# 4_serial_LSA.net
KiCad netlist of a schematic drawn in EAGLE
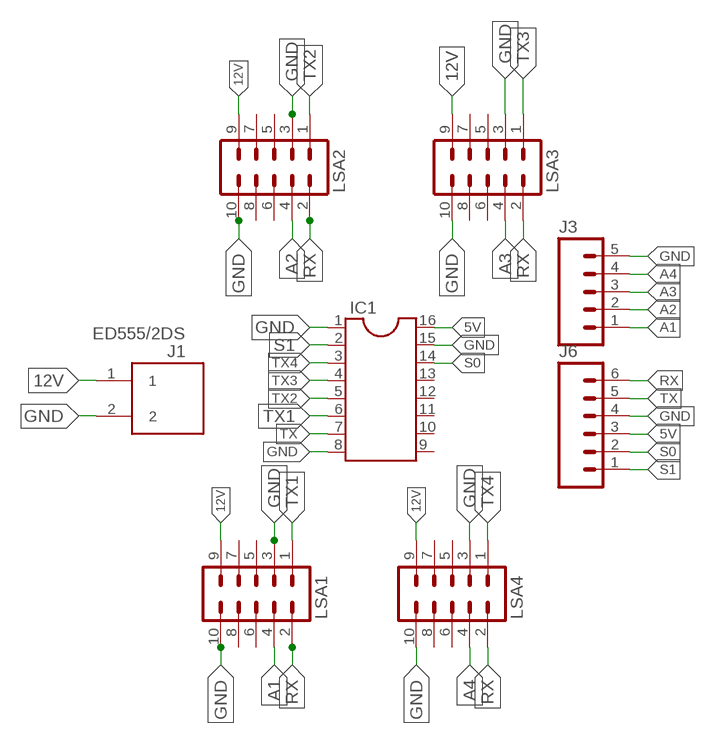
[diagram p0: schematic, sheet 1]

(export (version "E")
  (design (tool "Eeschema 10.0.6"))
  (components
    (comp (ref "IC1")
      (value "DIL16S")
      (footprint "eagle-import:SOCKET-16")
      (libsource (lib "eagle-import") (part "DIL16S"))
    )
    (comp (ref "J1")
      (value "ED555/2DS")
      (footprint "eagle-import:ED555_2DS")
      (libsource (lib "eagle-import") (part "ED555/2DS"))
    )
    (comp (ref "J3")
      (value "M05PTH")
      (footprint "eagle-import:1X05")
      (fields (field (name "SPICEPREFIX") "X"))
      (libsource (lib "eagle-import") (part "M05PTH"))
    )
    (comp (ref "J6")
      (value "M06SILK_FEMALE_PTH")
      (footprint "eagle-import:1X06")
      (libsource (lib "eagle-import") (part "M06SILK_FEMALE_PTH"))
    )
    (comp (ref "LSA1")
      (value "M05X2SHD_LOCK")
      (footprint "eagle-import:2X5-SHROUDED_LOCK")
      (libsource (lib "eagle-import") (part "M05X2SHD_LOCK"))
    )
    (comp (ref "LSA2")
      (value "M05X2SHD_LOCK")
      (footprint "eagle-import:2X5-SHROUDED_LOCK")
      (libsource (lib "eagle-import") (part "M05X2SHD_LOCK"))
    )
    (comp (ref "LSA3")
      (value "M05X2SHD_LOCK")
      (footprint "eagle-import:2X5-SHROUDED_LOCK")
      (libsource (lib "eagle-import") (part "M05X2SHD_LOCK"))
    )
    (comp (ref "LSA4")
      (value "M05X2SHD_LOCK")
      (footprint "eagle-import:2X5-SHROUDED_LOCK")
      (libsource (lib "eagle-import") (part "M05X2SHD_LOCK"))
    )
  )
  (nets
    (net (code "1") (name "5V") (class "Default")
      (node (ref "IC1") (pin "16") (pinfunction "16_16") (pintype "passive"))
      (node (ref "J6") (pin "3") (pinfunction "3_3") (pintype "passive"))
    )
    (net (code "2") (name "12V") (class "Default")
      (node (ref "J1") (pin "1") (pinfunction "1_1") (pintype "bidirectional"))
      (node (ref "LSA1") (pin "9") (pinfunction "9_9") (pintype "passive"))
      (node (ref "LSA2") (pin "9") (pinfunction "9_9") (pintype "passive"))
      (node (ref "LSA3") (pin "9") (pinfunction "9_9") (pintype "passive"))
      (node (ref "LSA4") (pin "9") (pinfunction "9_9") (pintype "passive"))
    )
    (net (code "3") (name "A1") (class "Default")
      (node (ref "J3") (pin "1") (pinfunction "1_1") (pintype "passive"))
      (node (ref "LSA1") (pin "4") (pinfunction "4_4") (pintype "passive"))
    )
    (net (code "4") (name "A2") (class "Default")
      (node (ref "J3") (pin "2") (pinfunction "2_2") (pintype "passive"))
      (node (ref "LSA2") (pin "4") (pinfunction "4_4") (pintype "passive"))
    )
    (net (code "5") (name "A3") (class "Default")
      (node (ref "J3") (pin "3") (pinfunction "3_3") (pintype "passive"))
      (node (ref "LSA3") (pin "4") (pinfunction "4_4") (pintype "passive"))
    )
    (net (code "6") (name "A4") (class "Default")
      (node (ref "J3") (pin "4") (pinfunction "4_4") (pintype "passive"))
      (node (ref "LSA4") (pin "4") (pinfunction "4_4") (pintype "passive"))
    )
    (net (code "7") (name "GND") (class "Default")
      (node (ref "IC1") (pin "1") (pinfunction "1_1") (pintype "passive"))
      (node (ref "IC1") (pin "15") (pinfunction "15_15") (pintype "passive"))
      (node (ref "IC1") (pin "8") (pinfunction "8_8") (pintype "passive"))
      (node (ref "J1") (pin "2") (pinfunction "2_2") (pintype "bidirectional"))
      (node (ref "J3") (pin "5") (pinfunction "5_5") (pintype "passive"))
      (node (ref "J6") (pin "4") (pinfunction "4_4") (pintype "passive"))
      (node (ref "LSA1") (pin "10") (pinfunction "10_10") (pintype "passive"))
      (node (ref "LSA1") (pin "3") (pinfunction "3_3") (pintype "passive"))
      (node (ref "LSA2") (pin "10") (pinfunction "10_10") (pintype "passive"))
      (node (ref "LSA2") (pin "3") (pinfunction "3_3") (pintype "passive"))
      (node (ref "LSA3") (pin "10") (pinfunction "10_10") (pintype "passive"))
      (node (ref "LSA3") (pin "3") (pinfunction "3_3") (pintype "passive"))
      (node (ref "LSA4") (pin "10") (pinfunction "10_10") (pintype "passive"))
      (node (ref "LSA4") (pin "3") (pinfunction "3_3") (pintype "passive"))
    )
    (net (code "8") (name "RX") (class "Default")
      (node (ref "J6") (pin "6") (pinfunction "6_6") (pintype "passive"))
      (node (ref "LSA1") (pin "2") (pinfunction "2_2") (pintype "passive"))
      (node (ref "LSA2") (pin "2") (pinfunction "2_2") (pintype "passive"))
      (node (ref "LSA3") (pin "2") (pinfunction "2_2") (pintype "passive"))
      (node (ref "LSA4") (pin "2") (pinfunction "2_2") (pintype "passive"))
    )
    (net (code "9") (name "S0") (class "Default")
      (node (ref "IC1") (pin "14") (pinfunction "14_14") (pintype "passive"))
      (node (ref "J6") (pin "2") (pinfunction "2_2") (pintype "passive"))
    )
    (net (code "10") (name "S1") (class "Default")
      (node (ref "IC1") (pin "2") (pinfunction "2_2") (pintype "passive"))
      (node (ref "J6") (pin "1") (pinfunction "1_1") (pintype "passive"))
    )
    (net (code "11") (name "TX") (class "Default")
      (node (ref "IC1") (pin "7") (pinfunction "7_7") (pintype "passive"))
      (node (ref "J6") (pin "5") (pinfunction "5_5") (pintype "passive"))
    )
    (net (code "12") (name "TX1") (class "Default")
      (node (ref "IC1") (pin "6") (pinfunction "6_6") (pintype "passive"))
      (node (ref "LSA1") (pin "1") (pinfunction "1_1") (pintype "passive"))
    )
    (net (code "13") (name "TX2") (class "Default")
      (node (ref "IC1") (pin "5") (pinfunction "5_5") (pintype "passive"))
      (node (ref "LSA2") (pin "1") (pinfunction "1_1") (pintype "passive"))
    )
    (net (code "14") (name "TX3") (class "Default")
      (node (ref "IC1") (pin "4") (pinfunction "4_4") (pintype "passive"))
      (node (ref "LSA3") (pin "1") (pinfunction "1_1") (pintype "passive"))
    )
    (net (code "15") (name "TX4") (class "Default")
      (node (ref "IC1") (pin "3") (pinfunction "3_3") (pintype "passive"))
      (node (ref "LSA4") (pin "1") (pinfunction "1_1") (pintype "passive"))
    )
    (net (code "16") (name "unconnected-(IC1-Pad9)") (class "Default")
      (node (ref "IC1") (pin "9") (pinfunction "9_9") (pintype "passive"))
    )
    (net (code "17") (name "unconnected-(IC1-Pad10)") (class "Default")
      (node (ref "IC1") (pin "10") (pinfunction "10_10") (pintype "passive"))
    )
    (net (code "18") (name "unconnected-(IC1-Pad11)") (class "Default")
      (node (ref "IC1") (pin "11") (pinfunction "11_11") (pintype "passive"))
    )
    (net (code "19") (name "unconnected-(IC1-Pad12)") (class "Default")
      (node (ref "IC1") (pin "12") (pinfunction "12_12") (pintype "passive"))
    )
    (net (code "20") (name "unconnected-(IC1-Pad13)") (class "Default")
      (node (ref "IC1") (pin "13") (pinfunction "13_13") (pintype "passive"))
    )
    (net (code "21") (name "unconnected-(LSA1-Pad5)") (class "Default")
      (node (ref "LSA1") (pin "5") (pinfunction "5_5") (pintype "passive"))
    )
    (net (code "22") (name "unconnected-(LSA1-Pad6)") (class "Default")
      (node (ref "LSA1") (pin "6") (pinfunction "6_6") (pintype "passive"))
    )
    (net (code "23") (name "unconnected-(LSA1-Pad7)") (class "Default")
      (node (ref "LSA1") (pin "7") (pinfunction "7_7") (pintype "passive"))
    )
    (net (code "24") (name "unconnected-(LSA1-Pad8)") (class "Default")
      (node (ref "LSA1") (pin "8") (pinfunction "8_8") (pintype "passive"))
    )
    (net (code "25") (name "unconnected-(LSA2-Pad5)") (class "Default")
      (node (ref "LSA2") (pin "5") (pinfunction "5_5") (pintype "passive"))
    )
    (net (code "26") (name "unconnected-(LSA2-Pad6)") (class "Default")
      (node (ref "LSA2") (pin "6") (pinfunction "6_6") (pintype "passive"))
    )
    (net (code "27") (name "unconnected-(LSA2-Pad7)") (class "Default")
      (node (ref "LSA2") (pin "7") (pinfunction "7_7") (pintype "passive"))
    )
    (net (code "28") (name "unconnected-(LSA2-Pad8)") (class "Default")
      (node (ref "LSA2") (pin "8") (pinfunction "8_8") (pintype "passive"))
    )
    (net (code "29") (name "unconnected-(LSA3-Pad5)") (class "Default")
      (node (ref "LSA3") (pin "5") (pinfunction "5_5") (pintype "passive"))
    )
    (net (code "30") (name "unconnected-(LSA3-Pad6)") (class "Default")
      (node (ref "LSA3") (pin "6") (pinfunction "6_6") (pintype "passive"))
    )
    (net (code "31") (name "unconnected-(LSA3-Pad7)") (class "Default")
      (node (ref "LSA3") (pin "7") (pinfunction "7_7") (pintype "passive"))
    )
    (net (code "32") (name "unconnected-(LSA3-Pad8)") (class "Default")
      (node (ref "LSA3") (pin "8") (pinfunction "8_8") (pintype "passive"))
    )
    (net (code "33") (name "unconnected-(LSA4-Pad5)") (class "Default")
      (node (ref "LSA4") (pin "5") (pinfunction "5_5") (pintype "passive"))
    )
    (net (code "34") (name "unconnected-(LSA4-Pad6)") (class "Default")
      (node (ref "LSA4") (pin "6") (pinfunction "6_6") (pintype "passive"))
    )
    (net (code "35") (name "unconnected-(LSA4-Pad7)") (class "Default")
      (node (ref "LSA4") (pin "7") (pinfunction "7_7") (pintype "passive"))
    )
    (net (code "36") (name "unconnected-(LSA4-Pad8)") (class "Default")
      (node (ref "LSA4") (pin "8") (pinfunction "8_8") (pintype "passive"))
    )
  )
)
